# sensnodeTXv4.net
KiCad netlist of a schematic drawn in EAGLE
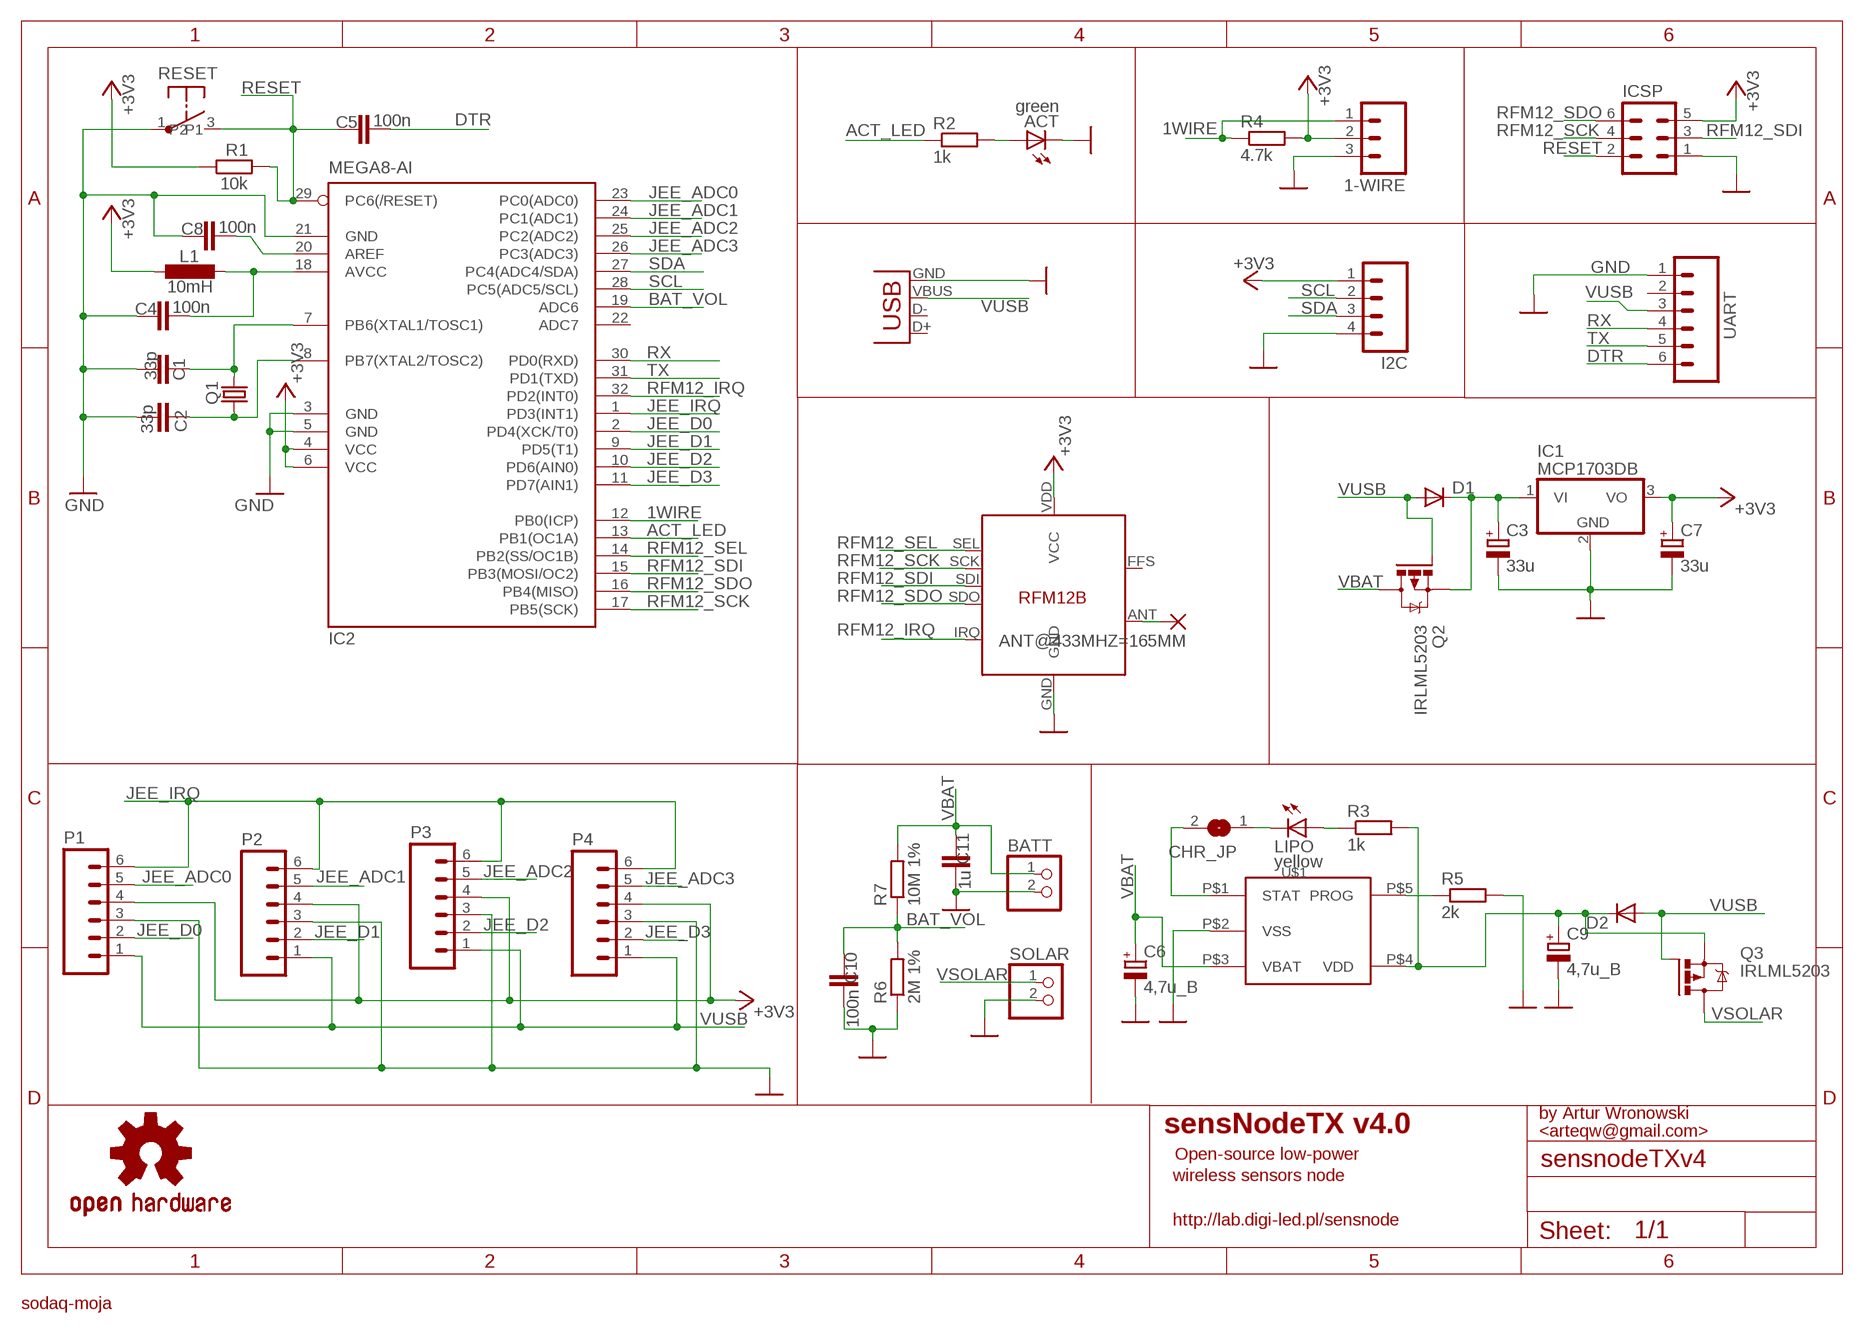
[diagram p0: schematic, sheet 1]

(export (version "E")
  (design (tool "Eeschema 10.0.6"))
  (components
    (comp (ref "1-WIRE")
      (value "M03LOCK")
      (footprint "eagle-import:1X03_LOCK")
      (libsource (lib "eagle-import") (part "M03LOCK"))
    )
    (comp (ref "ACT")
      (value "green")
      (footprint "eagle-import:1206")
      (libsource (lib "eagle-import") (part "LEDSMT1206"))
    )
    (comp (ref "ANT@433MHZ=165MM")
      (value "2,15/1,0")
      (footprint "eagle-import:2,15_1,0")
      (libsource (lib "eagle-import") (part "2,15/1,0"))
    )
    (comp (ref "BATT")
      (value "PINHD-1X2")
      (footprint "eagle-import:1X02")
      (libsource (lib "eagle-import") (part "PINHD-1X2"))
    )
    (comp (ref "C1")
      (value "33p")
      (footprint "eagle-import:C0805")
      (libsource (lib "eagle-import") (part "C-EUC0805"))
    )
    (comp (ref "C2")
      (value "33p")
      (footprint "eagle-import:C0805")
      (libsource (lib "eagle-import") (part "C-EUC0805"))
    )
    (comp (ref "C3")
      (value "33u")
      (footprint "eagle-import:SMC_B")
      (libsource (lib "eagle-import") (part "CPOL-EUSMCB"))
    )
    (comp (ref "C4")
      (value "100n")
      (footprint "eagle-import:C0805")
      (libsource (lib "eagle-import") (part "C-EUC0805"))
    )
    (comp (ref "C5")
      (value "100n")
      (footprint "eagle-import:C0805")
      (libsource (lib "eagle-import") (part "C-EUC0805"))
    )
    (comp (ref "C6")
      (value "4,7u_B")
      (footprint "eagle-import:SMC_B")
      (libsource (lib "eagle-import") (part "CPOL-EUSMCB"))
    )
    (comp (ref "C7")
      (value "33u")
      (footprint "eagle-import:SMC_B")
      (libsource (lib "eagle-import") (part "CPOL-EUSMCB"))
    )
    (comp (ref "C8")
      (value "100n")
      (footprint "eagle-import:C0805")
      (libsource (lib "eagle-import") (part "C-EUC0805"))
    )
    (comp (ref "C9")
      (value "4,7u_B")
      (footprint "eagle-import:SMC_B")
      (libsource (lib "eagle-import") (part "CPOL-EUSMCB"))
    )
    (comp (ref "C10")
      (value "100n")
      (footprint "eagle-import:C0805")
      (libsource (lib "eagle-import") (part "C-EUC0805"))
    )
    (comp (ref "C11")
      (value "1u")
      (footprint "eagle-import:C0805")
      (libsource (lib "eagle-import") (part "C-EUC0805"))
    )
    (comp (ref "CHR_JP")
      (value "JUMPER")
      (footprint "eagle-import:SJW")
      (libsource (lib "eagle-import") (part "JUMPER"))
    )
    (comp (ref "D1")
      (value "1n5819 melf")
      (footprint "eagle-import:MELF-MLL41")
      (libsource (lib "eagle-import") (part "DIODE-MELF-MLL41"))
    )
    (comp (ref "D2")
      (value "1n5819 melf")
      (footprint "eagle-import:MELF-MLL41")
      (libsource (lib "eagle-import") (part "DIODE-MELF-MLL41"))
    )
    (comp (ref "I2C")
      (value "M04LOCK")
      (footprint "eagle-import:1X04_LOCK")
      (libsource (lib "eagle-import") (part "M04LOCK"))
    )
    (comp (ref "IC1")
      (value "MCP1703DB")
      (footprint "eagle-import:SOT223")
      (libsource (lib "eagle-import") (part "MCP1703DB"))
    )
    (comp (ref "IC2")
      (value "MEGA8-AI")
      (footprint "eagle-import:TQFP32-08")
      (fields (field (name "MPN") "ATMEGA8-16AU"))
      (libsource (lib "eagle-import") (part "MEGA8-AI"))
    )
    (comp (ref "ICSP")
      (value "MA03-2")
      (footprint "eagle-import:MA03-2")
      (libsource (lib "eagle-import") (part "MA03-2"))
    )
    (comp (ref "L1")
      (value "10mH")
      (footprint "eagle-import:0207_7")
      (libsource (lib "eagle-import") (part "L-EU0207/7"))
    )
    (comp (ref "LIPO")
      (value "yellow")
      (footprint "eagle-import:1206")
      (libsource (lib "eagle-import") (part "LEDSMT1206"))
    )
    (comp (ref "P1")
      (value "M06SIP_LOCK")
      (footprint "eagle-import:1X06-SIP_LOCK")
      (libsource (lib "eagle-import") (part "M06SIP_LOCK"))
    )
    (comp (ref "P2")
      (value "M06SIP_LOCK")
      (footprint "eagle-import:1X06-SIP_LOCK")
      (libsource (lib "eagle-import") (part "M06SIP_LOCK"))
    )
    (comp (ref "P3")
      (value "M06SIP_LOCK")
      (footprint "eagle-import:1X06-SIP_LOCK")
      (libsource (lib "eagle-import") (part "M06SIP_LOCK"))
    )
    (comp (ref "P4")
      (value "M06SIP_LOCK")
      (footprint "eagle-import:1X06-SIP_LOCK")
      (libsource (lib "eagle-import") (part "M06SIP_LOCK"))
    )
    (comp (ref "Q1")
      (value "CRYSTALHC49U70")
      (footprint "eagle-import:HC49U70")
      (libsource (lib "eagle-import") (part "CRYSTALHC49U70"))
    )
    (comp (ref "Q2")
      (value "IRLML5203")
      (footprint "eagle-import:MICRO3")
      (libsource (lib "eagle-import") (part "IRLML5203"))
    )
    (comp (ref "Q3")
      (value "IRLML5203")
      (footprint "eagle-import:MICRO3")
      (libsource (lib "eagle-import") (part "IRLML5203"))
    )
    (comp (ref "R1")
      (value "10k")
      (footprint "eagle-import:M0805")
      (libsource (lib "eagle-import") (part "R-EU_M0805"))
    )
    (comp (ref "R2")
      (value "1k")
      (footprint "eagle-import:M0805")
      (libsource (lib "eagle-import") (part "R-EU_M0805"))
    )
    (comp (ref "R3")
      (value "1k")
      (footprint "eagle-import:M0805")
      (libsource (lib "eagle-import") (part "R-EU_M0805"))
    )
    (comp (ref "R4")
      (value "4.7k")
      (footprint "eagle-import:M0805")
      (libsource (lib "eagle-import") (part "R-EU_M0805"))
    )
    (comp (ref "R5")
      (value "2k")
      (footprint "eagle-import:M0805")
      (libsource (lib "eagle-import") (part "R-EU_M0805"))
    )
    (comp (ref "R6")
      (value "2M 1%")
      (footprint "eagle-import:M0805")
      (libsource (lib "eagle-import") (part "R-EU_M0805"))
    )
    (comp (ref "R7")
      (value "10M 1%")
      (footprint "eagle-import:M0805")
      (libsource (lib "eagle-import") (part "R-EU_M0805"))
    )
    (comp (ref "RESET")
      (value "TACT3X6")
      (footprint "eagle-import:TACK3X6")
      (libsource (lib "eagle-import") (part "TACT3X6"))
    )
    (comp (ref "RFM12B")
      (value "RFM12B")
      (footprint "eagle-import:RFM12B")
      (libsource (lib "eagle-import") (part "RFM12B"))
    )
    (comp (ref "SOLAR")
      (value "PINHD-1X2")
      (footprint "eagle-import:1X02")
      (libsource (lib "eagle-import") (part "PINHD-1X2"))
    )
    (comp (ref "U$1")
      (value "MCP73831")
      (footprint "eagle-import:5PIN_SOT23")
      (libsource (lib "eagle-import") (part "MCP73831"))
    )
    (comp (ref "U$3")
      (value "OSHW-LOGOM")
      (footprint "eagle-import:OSHW-LOGO-M")
      (libsource (lib "eagle-import") (part "OSHW-LOGOM"))
    )
    (comp (ref "UART")
      (value "M06SIP_LOCK")
      (footprint "eagle-import:1X06-SIP_LOCK")
      (libsource (lib "eagle-import") (part "M06SIP_LOCK"))
    )
    (comp (ref "USB_PWR")
      (value "USBSMD")
      (footprint "eagle-import:USB-MINIB")
      (libsource (lib "eagle-import") (part "USBSMD"))
    )
  )
  (nets
    (net (code "1") (name "+3V3") (class "Default")
      (node (ref "1-WIRE") (pin "2") (pinfunction "2_2") (pintype "passive"))
      (node (ref "C7") (pin "+") (pinfunction "+_+") (pintype "passive"))
      (node (ref "I2C") (pin "1") (pinfunction "1_1") (pintype "passive"))
      (node (ref "IC1") (pin "3") (pinfunction "VO_3") (pintype "passive"))
      (node (ref "IC2") (pin "4") (pinfunction "VCC_4") (pintype "power_in"))
      (node (ref "IC2") (pin "6") (pinfunction "VCC_6") (pintype "power_in"))
      (node (ref "ICSP") (pin "5") (pinfunction "5_5") (pintype "passive"))
      (node (ref "L1") (pin "1") (pinfunction "1_1") (pintype "passive"))
      (node (ref "P1") (pin "4") (pinfunction "4_4") (pintype "passive"))
      (node (ref "P2") (pin "4") (pinfunction "4_4") (pintype "passive"))
      (node (ref "P3") (pin "4") (pinfunction "4_4") (pintype "passive"))
      (node (ref "P4") (pin "4") (pinfunction "4_4") (pintype "passive"))
      (node (ref "R1") (pin "1") (pinfunction "1_1") (pintype "passive"))
      (node (ref "R4") (pin "2") (pinfunction "2_2") (pintype "passive"))
      (node (ref "RFM12B") (pin "VDD") (pinfunction "VCC_VDD") (pintype "power_in"))
    )
    (net (code "2") (name "/1WIRE") (class "Default")
      (node (ref "1-WIRE") (pin "1") (pinfunction "1_1") (pintype "passive"))
      (node (ref "IC2") (pin "12") (pinfunction "PB0(ICP)_12") (pintype "bidirectional"))
      (node (ref "R4") (pin "1") (pinfunction "1_1") (pintype "passive"))
    )
    (net (code "3") (name "/ACT_LED") (class "Default")
      (node (ref "IC2") (pin "13") (pinfunction "PB1(OC1A)_13") (pintype "bidirectional"))
      (node (ref "R2") (pin "1") (pinfunction "1_1") (pintype "passive"))
    )
    (net (code "4") (name "/BAT_VOL") (class "Default")
      (node (ref "C10") (pin "2") (pinfunction "2_2") (pintype "passive"))
      (node (ref "IC2") (pin "19") (pinfunction "ADC6_19") (pintype "bidirectional"))
      (node (ref "R6") (pin "2") (pinfunction "2_2") (pintype "passive"))
      (node (ref "R7") (pin "1") (pinfunction "1_1") (pintype "passive"))
    )
    (net (code "5") (name "/DTR") (class "Default")
      (node (ref "C5") (pin "1") (pinfunction "1_1") (pintype "passive"))
      (node (ref "UART") (pin "6") (pinfunction "6_6") (pintype "passive"))
    )
    (net (code "6") (name "/JEE_ADC0") (class "Default")
      (node (ref "IC2") (pin "23") (pinfunction "PC0(ADC0)_23") (pintype "bidirectional"))
      (node (ref "P1") (pin "5") (pinfunction "5_5") (pintype "passive"))
    )
    (net (code "7") (name "/JEE_ADC1") (class "Default")
      (node (ref "IC2") (pin "24") (pinfunction "PC1(ADC1)_24") (pintype "bidirectional"))
      (node (ref "P2") (pin "5") (pinfunction "5_5") (pintype "passive"))
    )
    (net (code "8") (name "/JEE_ADC2") (class "Default")
      (node (ref "IC2") (pin "25") (pinfunction "PC2(ADC2)_25") (pintype "bidirectional"))
      (node (ref "P3") (pin "5") (pinfunction "5_5") (pintype "passive"))
    )
    (net (code "9") (name "/JEE_ADC3") (class "Default")
      (node (ref "IC2") (pin "26") (pinfunction "PC3(ADC3)_26") (pintype "bidirectional"))
      (node (ref "P4") (pin "5") (pinfunction "5_5") (pintype "passive"))
    )
    (net (code "10") (name "/JEE_D0") (class "Default")
      (node (ref "IC2") (pin "2") (pinfunction "PD4(XCK/T0)_2") (pintype "bidirectional"))
      (node (ref "P1") (pin "2") (pinfunction "2_2") (pintype "passive"))
    )
    (net (code "11") (name "/JEE_D1") (class "Default")
      (node (ref "IC2") (pin "9") (pinfunction "PD5(T1)_9") (pintype "bidirectional"))
      (node (ref "P2") (pin "2") (pinfunction "2_2") (pintype "passive"))
    )
    (net (code "12") (name "/JEE_D2") (class "Default")
      (node (ref "IC2") (pin "10") (pinfunction "PD6(AIN0)_10") (pintype "bidirectional"))
      (node (ref "P3") (pin "2") (pinfunction "2_2") (pintype "passive"))
    )
    (net (code "13") (name "/JEE_D3") (class "Default")
      (node (ref "IC2") (pin "11") (pinfunction "PD7(AIN1)_11") (pintype "bidirectional"))
      (node (ref "P4") (pin "2") (pinfunction "2_2") (pintype "passive"))
    )
    (net (code "14") (name "/JEE_IRQ") (class "Default")
      (node (ref "IC2") (pin "1") (pinfunction "PD3(INT1)_1") (pintype "bidirectional"))
      (node (ref "P1") (pin "6") (pinfunction "6_6") (pintype "passive"))
      (node (ref "P2") (pin "6") (pinfunction "6_6") (pintype "passive"))
      (node (ref "P3") (pin "6") (pinfunction "6_6") (pintype "passive"))
      (node (ref "P4") (pin "6") (pinfunction "6_6") (pintype "passive"))
    )
    (net (code "15") (name "/RESET") (class "Default")
      (node (ref "C5") (pin "2") (pinfunction "2_2") (pintype "passive"))
      (node (ref "IC2") (pin "29") (pinfunction "PC6(/RESET)_29") (pintype "bidirectional"))
      (node (ref "ICSP") (pin "2") (pinfunction "2_2") (pintype "passive"))
      (node (ref "R1") (pin "2") (pinfunction "2_2") (pintype "passive"))
      (node (ref "RESET") (pin "3") (pinfunction "P2_3") (pintype "power_in"))
    )
    (net (code "16") (name "/RFM12_IRQ") (class "Default")
      (node (ref "IC2") (pin "32") (pinfunction "PD2(INT0)_32") (pintype "bidirectional"))
      (node (ref "RFM12B") (pin "IRQ") (pinfunction "IRQ_IRQ") (pintype "open_collector"))
    )
    (net (code "17") (name "/RFM12_SCK") (class "Default")
      (node (ref "IC2") (pin "17") (pinfunction "PB5(SCK)_17") (pintype "bidirectional"))
      (node (ref "ICSP") (pin "4") (pinfunction "4_4") (pintype "passive"))
      (node (ref "RFM12B") (pin "SCK") (pinfunction "SCK_SCK") (pintype "input"))
    )
    (net (code "18") (name "/RFM12_SDI") (class "Default")
      (node (ref "IC2") (pin "15") (pinfunction "PB3(MOSI/OC2)_15") (pintype "bidirectional"))
      (node (ref "ICSP") (pin "3") (pinfunction "3_3") (pintype "passive"))
      (node (ref "RFM12B") (pin "SDI") (pinfunction "SDI_SDI") (pintype "input"))
    )
    (net (code "19") (name "/RFM12_SDO") (class "Default")
      (node (ref "IC2") (pin "16") (pinfunction "PB4(MISO)_16") (pintype "bidirectional"))
      (node (ref "ICSP") (pin "6") (pinfunction "6_6") (pintype "passive"))
      (node (ref "RFM12B") (pin "SDO") (pinfunction "SDO_SDO") (pintype "output"))
    )
    (net (code "20") (name "/RFM12_SEL") (class "Default")
      (node (ref "IC2") (pin "14") (pinfunction "PB2(SS/OC1B)_14") (pintype "bidirectional"))
      (node (ref "RFM12B") (pin "SEL") (pinfunction "SEL_SEL") (pintype "input"))
    )
    (net (code "21") (name "/RX") (class "Default")
      (node (ref "IC2") (pin "30") (pinfunction "PD0(RXD)_30") (pintype "bidirectional"))
      (node (ref "UART") (pin "4") (pinfunction "4_4") (pintype "passive"))
    )
    (net (code "22") (name "/SCL") (class "Default")
      (node (ref "I2C") (pin "2") (pinfunction "2_2") (pintype "passive"))
      (node (ref "IC2") (pin "28") (pinfunction "PC5(ADC5/SCL)_28") (pintype "bidirectional"))
    )
    (net (code "23") (name "/SDA") (class "Default")
      (node (ref "I2C") (pin "3") (pinfunction "3_3") (pintype "passive"))
      (node (ref "IC2") (pin "27") (pinfunction "PC4(ADC4/SDA)_27") (pintype "bidirectional"))
    )
    (net (code "24") (name "/TX") (class "Default")
      (node (ref "IC2") (pin "31") (pinfunction "PD1(TXD)_31") (pintype "bidirectional"))
      (node (ref "UART") (pin "5") (pinfunction "5_5") (pintype "passive"))
    )
    (net (code "25") (name "/VBAT") (class "Default")
      (node (ref "BATT") (pin "1") (pinfunction "1_1") (pintype "passive"))
      (node (ref "C11") (pin "2") (pinfunction "2_2") (pintype "passive"))
      (node (ref "C6") (pin "+") (pinfunction "+_+") (pintype "passive"))
      (node (ref "Q2") (pin "3") (pinfunction "D_3") (pintype "passive"))
      (node (ref "R7") (pin "2") (pinfunction "2_2") (pintype "passive"))
      (node (ref "U$1") (pin "P$3") (pinfunction "VBAT_P$3") (pintype "bidirectional"))
    )
    (net (code "26") (name "/VSOLAR") (class "Default")
      (node (ref "Q3") (pin "3") (pinfunction "D_3") (pintype "passive"))
      (node (ref "SOLAR") (pin "1") (pinfunction "1_1") (pintype "passive"))
    )
    (net (code "27") (name "/VUSB") (class "Default")
      (node (ref "D1") (pin "A") (pinfunction "A_A") (pintype "passive"))
      (node (ref "D2") (pin "A") (pinfunction "A_A") (pintype "passive"))
      (node (ref "P1") (pin "1") (pinfunction "1_1") (pintype "passive"))
      (node (ref "P2") (pin "1") (pinfunction "1_1") (pintype "passive"))
      (node (ref "P3") (pin "1") (pinfunction "1_1") (pintype "passive"))
      (node (ref "P4") (pin "1") (pinfunction "1_1") (pintype "passive"))
      (node (ref "Q2") (pin "1") (pinfunction "G_1") (pintype "passive"))
      (node (ref "Q3") (pin "1") (pinfunction "G_1") (pintype "passive"))
      (node (ref "UART") (pin "3") (pinfunction "3_3") (pintype "passive"))
      (node (ref "USB_PWR") (pin "VBUS") (pinfunction "VBUS_VBUS") (pintype "bidirectional"))
    )
    (net (code "28") (name "GND") (class "Default")
      (node (ref "1-WIRE") (pin "3") (pinfunction "3_3") (pintype "passive"))
      (node (ref "ACT") (pin "C") (pinfunction "C_C") (pintype "passive"))
      (node (ref "BATT") (pin "2") (pinfunction "2_2") (pintype "passive"))
      (node (ref "C1") (pin "2") (pinfunction "2_2") (pintype "passive"))
      (node (ref "C10") (pin "1") (pinfunction "1_1") (pintype "passive"))
      (node (ref "C11") (pin "1") (pinfunction "1_1") (pintype "passive"))
      (node (ref "C2") (pin "2") (pinfunction "2_2") (pintype "passive"))
      (node (ref "C3") (pin "-") (pinfunction "-_-") (pintype "passive"))
      (node (ref "C4") (pin "2") (pinfunction "2_2") (pintype "passive"))
      (node (ref "C6") (pin "-") (pinfunction "-_-") (pintype "passive"))
      (node (ref "C7") (pin "-") (pinfunction "-_-") (pintype "passive"))
      (node (ref "C8") (pin "2") (pinfunction "2_2") (pintype "passive"))
      (node (ref "C9") (pin "-") (pinfunction "-_-") (pintype "passive"))
      (node (ref "I2C") (pin "4") (pinfunction "4_4") (pintype "passive"))
      (node (ref "IC1") (pin "2") (pinfunction "GND_2") (pintype "passive"))
      (node (ref "IC2") (pin "21") (pinfunction "GND_21") (pintype "power_in"))
      (node (ref "IC2") (pin "3") (pinfunction "GND_3") (pintype "power_in"))
      (node (ref "IC2") (pin "5") (pinfunction "GND_5") (pintype "power_in"))
      (node (ref "ICSP") (pin "1") (pinfunction "1_1") (pintype "passive"))
      (node (ref "P1") (pin "3") (pinfunction "3_3") (pintype "passive"))
      (node (ref "P2") (pin "3") (pinfunction "3_3") (pintype "passive"))
      (node (ref "P3") (pin "3") (pinfunction "3_3") (pintype "passive"))
      (node (ref "P4") (pin "3") (pinfunction "3_3") (pintype "passive"))
      (node (ref "R5") (pin "2") (pinfunction "2_2") (pintype "passive"))
      (node (ref "R6") (pin "1") (pinfunction "1_1") (pintype "passive"))
      (node (ref "RESET") (pin "1") (pinfunction "P1_1") (pintype "power_in"))
      (node (ref "RFM12B") (pin "GND") (pinfunction "GND_GND") (pintype "power_in"))
      (node (ref "SOLAR") (pin "2") (pinfunction "2_2") (pintype "passive"))
      (node (ref "U$1") (pin "P$2") (pinfunction "VSS_P$2") (pintype "bidirectional"))
      (node (ref "UART") (pin "1") (pinfunction "1_1") (pintype "passive"))
      (node (ref "USB_PWR") (pin "GND") (pinfunction "GND_GND") (pintype "bidirectional"))
    )
    (net (code "29") (name "Net-(ACT-PadA)") (class "Default")
      (node (ref "ACT") (pin "A") (pinfunction "A_A") (pintype "passive"))
      (node (ref "R2") (pin "2") (pinfunction "2_2") (pintype "passive"))
    )
    (net (code "30") (name "Net-(ANT@433MHZ=165MM-P)") (class "Default")
      (node (ref "ANT@433MHZ=165MM") (pin "1") (pinfunction "P_1") (pintype "passive"))
      (node (ref "RFM12B") (pin "ANT") (pinfunction "ANT_ANT") (pintype "passive"))
    )
    (net (code "31") (name "Net-(CHR_JP-Pad1)") (class "Default")
      (node (ref "CHR_JP") (pin "1") (pinfunction "1_1") (pintype "passive"))
      (node (ref "LIPO") (pin "C") (pinfunction "C_C") (pintype "passive"))
    )
    (net (code "32") (name "Net-(IC1-VI)") (class "Default")
      (node (ref "C3") (pin "+") (pinfunction "+_+") (pintype "passive"))
      (node (ref "D1") (pin "C") (pinfunction "C_C") (pintype "passive"))
      (node (ref "IC1") (pin "1") (pinfunction "VI_1") (pintype "input"))
      (node (ref "Q2") (pin "2") (pinfunction "S_2") (pintype "passive"))
    )
    (net (code "33") (name "Net-(IC2-AREF)") (class "Default")
      (node (ref "C8") (pin "1") (pinfunction "1_1") (pintype "passive"))
      (node (ref "IC2") (pin "20") (pinfunction "AREF_20") (pintype "passive"))
    )
    (net (code "34") (name "Net-(IC2-AVCC)") (class "Default")
      (node (ref "C4") (pin "1") (pinfunction "1_1") (pintype "passive"))
      (node (ref "IC2") (pin "18") (pinfunction "AVCC_18") (pintype "power_in"))
      (node (ref "L1") (pin "2") (pinfunction "2_2") (pintype "passive"))
    )
    (net (code "35") (name "Net-(IC2-PB6(XTAL1{slash}TOSC1))") (class "Default")
      (node (ref "C1") (pin "1") (pinfunction "1_1") (pintype "passive"))
      (node (ref "IC2") (pin "7") (pinfunction "PB6(XTAL1/TOSC1)_7") (pintype "bidirectional"))
      (node (ref "Q1") (pin "2") (pinfunction "2_2") (pintype "passive"))
    )
    (net (code "36") (name "Net-(IC2-PB7(XTAL2{slash}TOSC2))") (class "Default")
      (node (ref "C2") (pin "1") (pinfunction "1_1") (pintype "passive"))
      (node (ref "IC2") (pin "8") (pinfunction "PB7(XTAL2/TOSC2)_8") (pintype "bidirectional"))
      (node (ref "Q1") (pin "1") (pinfunction "1_1") (pintype "passive"))
    )
    (net (code "37") (name "Net-(LIPO-PadA)") (class "Default")
      (node (ref "LIPO") (pin "A") (pinfunction "A_A") (pintype "passive"))
      (node (ref "R3") (pin "1") (pinfunction "1_1") (pintype "passive"))
    )
    (net (code "38") (name "Net-(Q3-S)") (class "Default")
      (node (ref "C9") (pin "+") (pinfunction "+_+") (pintype "passive"))
      (node (ref "D2") (pin "C") (pinfunction "C_C") (pintype "passive"))
      (node (ref "Q3") (pin "2") (pinfunction "S_2") (pintype "passive"))
      (node (ref "R3") (pin "2") (pinfunction "2_2") (pintype "passive"))
      (node (ref "U$1") (pin "P$4") (pinfunction "VDD_P$4") (pintype "bidirectional"))
    )
    (net (code "39") (name "Net-(U$1-PROG)") (class "Default")
      (node (ref "R5") (pin "1") (pinfunction "1_1") (pintype "passive"))
      (node (ref "U$1") (pin "P$5") (pinfunction "PROG_P$5") (pintype "bidirectional"))
    )
    (net (code "40") (name "Net-(U$1-STAT)") (class "Default")
      (node (ref "CHR_JP") (pin "2") (pinfunction "2_2") (pintype "passive"))
      (node (ref "U$1") (pin "P$1") (pinfunction "STAT_P$1") (pintype "bidirectional"))
    )
    (net (code "41") (name "unconnected-(IC2-ADC7-Pad22)") (class "Default")
      (node (ref "IC2") (pin "22") (pinfunction "ADC7_22") (pintype "bidirectional"))
    )
    (net (code "42") (name "unconnected-(RFM12B-PadFFS)") (class "Default")
      (node (ref "RFM12B") (pin "FFS") (pinfunction "FFS_FFS") (pintype "bidirectional"))
    )
    (net (code "43") (name "unconnected-(UART-Pad2)") (class "Default")
      (node (ref "UART") (pin "2") (pinfunction "2_2") (pintype "passive"))
    )
    (net (code "44") (name "unconnected-(USB_PWR-PadD+)") (class "Default")
      (node (ref "USB_PWR") (pin "D+") (pinfunction "D+_D+") (pintype "bidirectional"))
    )
    (net (code "45") (name "unconnected-(USB_PWR-PadD-)") (class "Default")
      (node (ref "USB_PWR") (pin "D-") (pinfunction "D-_D-") (pintype "bidirectional"))
    )
  )
)
